# serial-converter.net
KiCad netlist of a schematic drawn in EAGLE
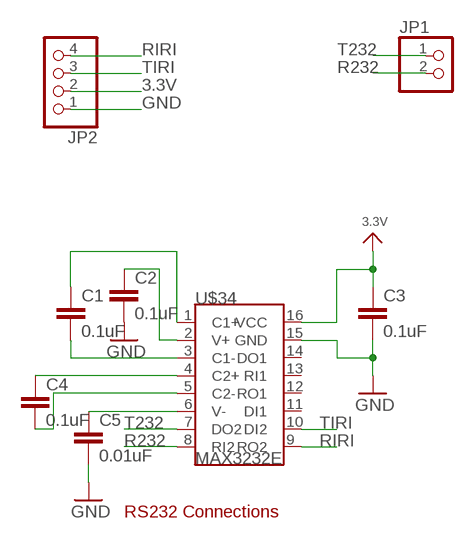
[diagram p0: schematic, sheet 1]

(export (version "E")
  (design (tool "Eeschema 10.0.6"))
  (components
    (comp (ref "C1")
      (value "0.1uF")
      (footprint "eagle-import:C0603")
      (libsource (lib "eagle-import") (part "C-EUC0603"))
    )
    (comp (ref "C2")
      (value "0.1uF")
      (footprint "eagle-import:C0603")
      (libsource (lib "eagle-import") (part "C-EUC0603"))
    )
    (comp (ref "C3")
      (value "0.1uF")
      (footprint "eagle-import:C0603")
      (libsource (lib "eagle-import") (part "C-EUC0603"))
    )
    (comp (ref "C4")
      (value "0.1uF")
      (footprint "eagle-import:C0603")
      (libsource (lib "eagle-import") (part "C-EUC0603"))
    )
    (comp (ref "C5")
      (value "0.01uF")
      (footprint "eagle-import:C0603")
      (libsource (lib "eagle-import") (part "C-EUC0603"))
    )
    (comp (ref "JP1")
      (value "PINHD-1X2")
      (footprint "eagle-import:1X02")
      (libsource (lib "eagle-import") (part "PINHD-1X2"))
    )
    (comp (ref "JP2")
      (value "PINHD-1X4")
      (footprint "eagle-import:1X04")
      (libsource (lib "eagle-import") (part "PINHD-1X4"))
    )
    (comp (ref "U$34")
      (value "MAX3232E")
      (footprint "eagle-import:SSOP-16")
      (libsource (lib "eagle-import") (part "MAX3232E"))
    )
  )
  (nets
    (net (code "1") (name "/R232") (class "Default")
      (node (ref "JP1") (pin "2") (pinfunction "2_2") (pintype "passive"))
      (node (ref "U$34") (pin "8") (pinfunction "RI2_8") (pintype "bidirectional"))
    )
    (net (code "2") (name "/RIRI") (class "Default")
      (node (ref "JP2") (pin "4") (pinfunction "4_4") (pintype "passive"))
      (node (ref "U$34") (pin "9") (pinfunction "RO2_9") (pintype "bidirectional"))
    )
    (net (code "3") (name "/T232") (class "Default")
      (node (ref "JP1") (pin "1") (pinfunction "1_1") (pintype "passive"))
      (node (ref "U$34") (pin "7") (pinfunction "DO2_7") (pintype "bidirectional"))
    )
    (net (code "4") (name "/TIRI") (class "Default")
      (node (ref "JP2") (pin "3") (pinfunction "3_3") (pintype "passive"))
      (node (ref "U$34") (pin "10") (pinfunction "DI2_10") (pintype "bidirectional"))
    )
    (net (code "5") (name "3.3V") (class "Default")
      (node (ref "C3") (pin "1") (pinfunction "1_1") (pintype "passive"))
      (node (ref "JP2") (pin "2") (pinfunction "2_2") (pintype "passive"))
      (node (ref "U$34") (pin "16") (pinfunction "VCC_16") (pintype "bidirectional"))
    )
    (net (code "6") (name "GND") (class "Default")
      (node (ref "C2") (pin "2") (pinfunction "2_2") (pintype "passive"))
      (node (ref "C3") (pin "2") (pinfunction "2_2") (pintype "passive"))
      (node (ref "C5") (pin "2") (pinfunction "2_2") (pintype "passive"))
      (node (ref "JP2") (pin "1") (pinfunction "1_1") (pintype "passive"))
      (node (ref "U$34") (pin "15") (pinfunction "GND_15") (pintype "bidirectional"))
    )
    (net (code "7") (name "Net-(U$34-C1+)") (class "Default")
      (node (ref "C1") (pin "1") (pinfunction "1_1") (pintype "passive"))
      (node (ref "U$34") (pin "1") (pinfunction "C1+_1") (pintype "bidirectional"))
    )
    (net (code "8") (name "Net-(U$34-C1-)") (class "Default")
      (node (ref "C1") (pin "2") (pinfunction "2_2") (pintype "passive"))
      (node (ref "U$34") (pin "3") (pinfunction "C1-_3") (pintype "bidirectional"))
    )
    (net (code "9") (name "Net-(U$34-C2+)") (class "Default")
      (node (ref "C4") (pin "1") (pinfunction "1_1") (pintype "passive"))
      (node (ref "U$34") (pin "4") (pinfunction "C2+_4") (pintype "bidirectional"))
    )
    (net (code "10") (name "Net-(U$34-C2-)") (class "Default")
      (node (ref "C4") (pin "2") (pinfunction "2_2") (pintype "passive"))
      (node (ref "U$34") (pin "5") (pinfunction "C2-_5") (pintype "bidirectional"))
    )
    (net (code "11") (name "Net-(U$34-V+)") (class "Default")
      (node (ref "C2") (pin "1") (pinfunction "1_1") (pintype "passive"))
      (node (ref "U$34") (pin "2") (pinfunction "V+_2") (pintype "bidirectional"))
    )
    (net (code "12") (name "Net-(U$34-V-)") (class "Default")
      (node (ref "C5") (pin "1") (pinfunction "1_1") (pintype "passive"))
      (node (ref "U$34") (pin "6") (pinfunction "V-_6") (pintype "bidirectional"))
    )
    (net (code "13") (name "unconnected-(U$34-DI1-Pad11)") (class "Default")
      (node (ref "U$34") (pin "11") (pinfunction "DI1_11") (pintype "bidirectional"))
    )
    (net (code "14") (name "unconnected-(U$34-DO1-Pad14)") (class "Default")
      (node (ref "U$34") (pin "14") (pinfunction "DO1_14") (pintype "bidirectional"))
    )
    (net (code "15") (name "unconnected-(U$34-RI1-Pad13)") (class "Default")
      (node (ref "U$34") (pin "13") (pinfunction "RI1_13") (pintype "bidirectional"))
    )
    (net (code "16") (name "unconnected-(U$34-RO1-Pad12)") (class "Default")
      (node (ref "U$34") (pin "12") (pinfunction "RO1_12") (pintype "bidirectional"))
    )
  )
)
